# LED1_con.net
KiCad netlist of a schematic drawn in EAGLE
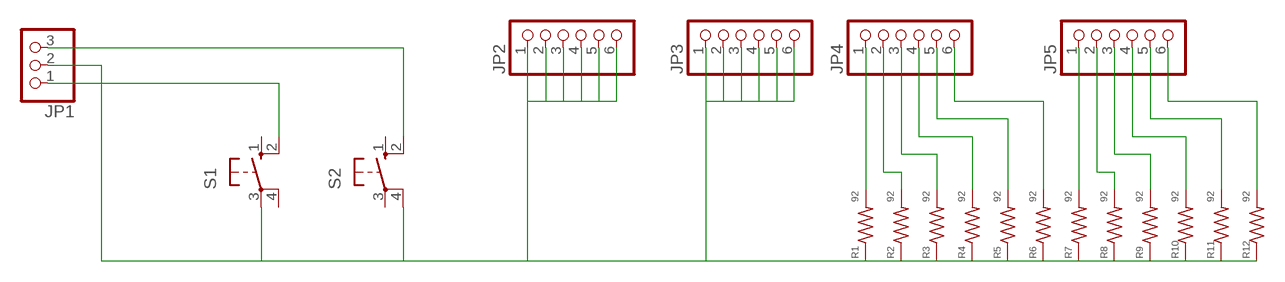
[diagram p0: schematic, sheet 1]

(export (version "E")
  (design (tool "Eeschema 10.0.6"))
  (components
    (comp (ref "JP1")
      (value "PINHD-1X3")
      (footprint "eagle-import:1X03")
      (libsource (lib "eagle-import") (part "PINHD-1X3"))
    )
    (comp (ref "JP2")
      (value "PINHD-1X6")
      (footprint "eagle-import:1X06")
      (libsource (lib "eagle-import") (part "PINHD-1X6"))
    )
    (comp (ref "JP3")
      (value "PINHD-1X6")
      (footprint "eagle-import:1X06")
      (libsource (lib "eagle-import") (part "PINHD-1X6"))
    )
    (comp (ref "JP4")
      (value "PINHD-1X6")
      (footprint "eagle-import:1X06")
      (libsource (lib "eagle-import") (part "PINHD-1X6"))
    )
    (comp (ref "JP5")
      (value "PINHD-1X6")
      (footprint "eagle-import:1X06")
      (libsource (lib "eagle-import") (part "PINHD-1X6"))
    )
    (comp (ref "R1")
      (value "92")
      (footprint "eagle-import:R1206")
      (libsource (lib "eagle-import") (part "R-US_R1206"))
    )
    (comp (ref "R2")
      (value "92")
      (footprint "eagle-import:R1206")
      (libsource (lib "eagle-import") (part "R-US_R1206"))
    )
    (comp (ref "R3")
      (value "92")
      (footprint "eagle-import:R1206")
      (libsource (lib "eagle-import") (part "R-US_R1206"))
    )
    (comp (ref "R4")
      (value "92")
      (footprint "eagle-import:R1206")
      (libsource (lib "eagle-import") (part "R-US_R1206"))
    )
    (comp (ref "R5")
      (value "92")
      (footprint "eagle-import:R1206")
      (libsource (lib "eagle-import") (part "R-US_R1206"))
    )
    (comp (ref "R6")
      (value "92")
      (footprint "eagle-import:R1206")
      (libsource (lib "eagle-import") (part "R-US_R1206"))
    )
    (comp (ref "R7")
      (value "92")
      (footprint "eagle-import:R1206")
      (libsource (lib "eagle-import") (part "R-US_R1206"))
    )
    (comp (ref "R8")
      (value "92")
      (footprint "eagle-import:R1206")
      (libsource (lib "eagle-import") (part "R-US_R1206"))
    )
    (comp (ref "R9")
      (value "92")
      (footprint "eagle-import:R1206")
      (libsource (lib "eagle-import") (part "R-US_R1206"))
    )
    (comp (ref "R10")
      (value "92")
      (footprint "eagle-import:R1206")
      (libsource (lib "eagle-import") (part "R-US_R1206"))
    )
    (comp (ref "R11")
      (value "92")
      (footprint "eagle-import:R1206")
      (libsource (lib "eagle-import") (part "R-US_R1206"))
    )
    (comp (ref "R12")
      (value "92")
      (footprint "eagle-import:R1206")
      (libsource (lib "eagle-import") (part "R-US_R1206"))
    )
    (comp (ref "S1")
      (value "10-XX")
      (footprint "eagle-import:B3F-10XX")
      (libsource (lib "eagle-import") (part "10-XX"))
    )
    (comp (ref "S2")
      (value "10-XX")
      (footprint "eagle-import:B3F-10XX")
      (libsource (lib "eagle-import") (part "10-XX"))
    )
  )
  (nets
    (net (code "1") (name "Net-(JP4-Pad1)") (class "Default")
      (node (ref "JP4") (pin "1") (pinfunction "1_1") (pintype "passive"))
      (node (ref "R1") (pin "2") (pinfunction "2_2") (pintype "passive"))
    )
    (net (code "2") (name "Net-(JP4-Pad2)") (class "Default")
      (node (ref "JP4") (pin "2") (pinfunction "2_2") (pintype "passive"))
      (node (ref "R2") (pin "2") (pinfunction "2_2") (pintype "passive"))
    )
    (net (code "3") (name "Net-(JP4-Pad3)") (class "Default")
      (node (ref "JP4") (pin "3") (pinfunction "3_3") (pintype "passive"))
      (node (ref "R3") (pin "2") (pinfunction "2_2") (pintype "passive"))
    )
    (net (code "4") (name "Net-(JP4-Pad4)") (class "Default")
      (node (ref "JP4") (pin "4") (pinfunction "4_4") (pintype "passive"))
      (node (ref "R4") (pin "2") (pinfunction "2_2") (pintype "passive"))
    )
    (net (code "5") (name "Net-(JP4-Pad5)") (class "Default")
      (node (ref "JP4") (pin "5") (pinfunction "5_5") (pintype "passive"))
      (node (ref "R5") (pin "2") (pinfunction "2_2") (pintype "passive"))
    )
    (net (code "6") (name "Net-(JP4-Pad6)") (class "Default")
      (node (ref "JP4") (pin "6") (pinfunction "6_6") (pintype "passive"))
      (node (ref "R6") (pin "2") (pinfunction "2_2") (pintype "passive"))
    )
    (net (code "7") (name "Net-(JP5-Pad1)") (class "Default")
      (node (ref "JP5") (pin "1") (pinfunction "1_1") (pintype "passive"))
      (node (ref "R7") (pin "2") (pinfunction "2_2") (pintype "passive"))
    )
    (net (code "8") (name "Net-(JP5-Pad2)") (class "Default")
      (node (ref "JP5") (pin "2") (pinfunction "2_2") (pintype "passive"))
      (node (ref "R8") (pin "2") (pinfunction "2_2") (pintype "passive"))
    )
    (net (code "9") (name "Net-(JP5-Pad3)") (class "Default")
      (node (ref "JP5") (pin "3") (pinfunction "3_3") (pintype "passive"))
      (node (ref "R9") (pin "2") (pinfunction "2_2") (pintype "passive"))
    )
    (net (code "10") (name "Net-(JP5-Pad4)") (class "Default")
      (node (ref "JP5") (pin "4") (pinfunction "4_4") (pintype "passive"))
      (node (ref "R10") (pin "2") (pinfunction "2_2") (pintype "passive"))
    )
    (net (code "11") (name "Net-(JP5-Pad5)") (class "Default")
      (node (ref "JP5") (pin "5") (pinfunction "5_5") (pintype "passive"))
      (node (ref "R11") (pin "2") (pinfunction "2_2") (pintype "passive"))
    )
    (net (code "12") (name "Net-(JP5-Pad6)") (class "Default")
      (node (ref "JP5") (pin "6") (pinfunction "6_6") (pintype "passive"))
      (node (ref "R12") (pin "2") (pinfunction "2_2") (pintype "passive"))
    )
    (net (code "13") (name "Net-(S1-P)") (class "Default")
      (node (ref "JP1") (pin "2") (pinfunction "2_2") (pintype "passive"))
      (node (ref "JP2") (pin "1") (pinfunction "1_1") (pintype "passive"))
      (node (ref "JP2") (pin "2") (pinfunction "2_2") (pintype "passive"))
      (node (ref "JP2") (pin "3") (pinfunction "3_3") (pintype "passive"))
      (node (ref "JP2") (pin "4") (pinfunction "4_4") (pintype "passive"))
      (node (ref "JP2") (pin "5") (pinfunction "5_5") (pintype "passive"))
      (node (ref "JP2") (pin "6") (pinfunction "6_6") (pintype "passive"))
      (node (ref "JP3") (pin "1") (pinfunction "1_1") (pintype "passive"))
      (node (ref "JP3") (pin "2") (pinfunction "2_2") (pintype "passive"))
      (node (ref "JP3") (pin "3") (pinfunction "3_3") (pintype "passive"))
      (node (ref "JP3") (pin "4") (pinfunction "4_4") (pintype "passive"))
      (node (ref "JP3") (pin "5") (pinfunction "5_5") (pintype "passive"))
      (node (ref "JP3") (pin "6") (pinfunction "6_6") (pintype "passive"))
      (node (ref "R1") (pin "1") (pinfunction "1_1") (pintype "passive"))
      (node (ref "R10") (pin "1") (pinfunction "1_1") (pintype "passive"))
      (node (ref "R11") (pin "1") (pinfunction "1_1") (pintype "passive"))
      (node (ref "R12") (pin "1") (pinfunction "1_1") (pintype "passive"))
      (node (ref "R2") (pin "1") (pinfunction "1_1") (pintype "passive"))
      (node (ref "R3") (pin "1") (pinfunction "1_1") (pintype "passive"))
      (node (ref "R4") (pin "1") (pinfunction "1_1") (pintype "passive"))
      (node (ref "R5") (pin "1") (pinfunction "1_1") (pintype "passive"))
      (node (ref "R6") (pin "1") (pinfunction "1_1") (pintype "passive"))
      (node (ref "R7") (pin "1") (pinfunction "1_1") (pintype "passive"))
      (node (ref "R8") (pin "1") (pinfunction "1_1") (pintype "passive"))
      (node (ref "R9") (pin "1") (pinfunction "1_1") (pintype "passive"))
      (node (ref "S1") (pin "3") (pinfunction "P_3") (pintype "passive"))
      (node (ref "S2") (pin "4") (pinfunction "P1_4") (pintype "passive"))
    )
    (net (code "14") (name "Net-(S1-S1)") (class "Default")
      (node (ref "JP1") (pin "1") (pinfunction "1_1") (pintype "passive"))
      (node (ref "S1") (pin "2") (pinfunction "S1_2") (pintype "passive"))
    )
    (net (code "15") (name "Net-(S2-S1)") (class "Default")
      (node (ref "JP1") (pin "3") (pinfunction "3_3") (pintype "passive"))
      (node (ref "S2") (pin "2") (pinfunction "S1_2") (pintype "passive"))
    )
    (net (code "16") (name "unconnected-(S1-P1-Pad4)") (class "Default")
      (node (ref "S1") (pin "4") (pinfunction "P1_4") (pintype "passive"))
    )
    (net (code "17") (name "unconnected-(S1-S-Pad1)") (class "Default")
      (node (ref "S1") (pin "1") (pinfunction "S_1") (pintype "passive"))
    )
    (net (code "18") (name "unconnected-(S2-P-Pad3)") (class "Default")
      (node (ref "S2") (pin "3") (pinfunction "P_3") (pintype "passive"))
    )
    (net (code "19") (name "unconnected-(S2-S-Pad1)") (class "Default")
      (node (ref "S2") (pin "1") (pinfunction "S_1") (pintype "passive"))
    )
  )
)
